# BendulumClockShield.net
KiCad netlist of a schematic drawn in EAGLE
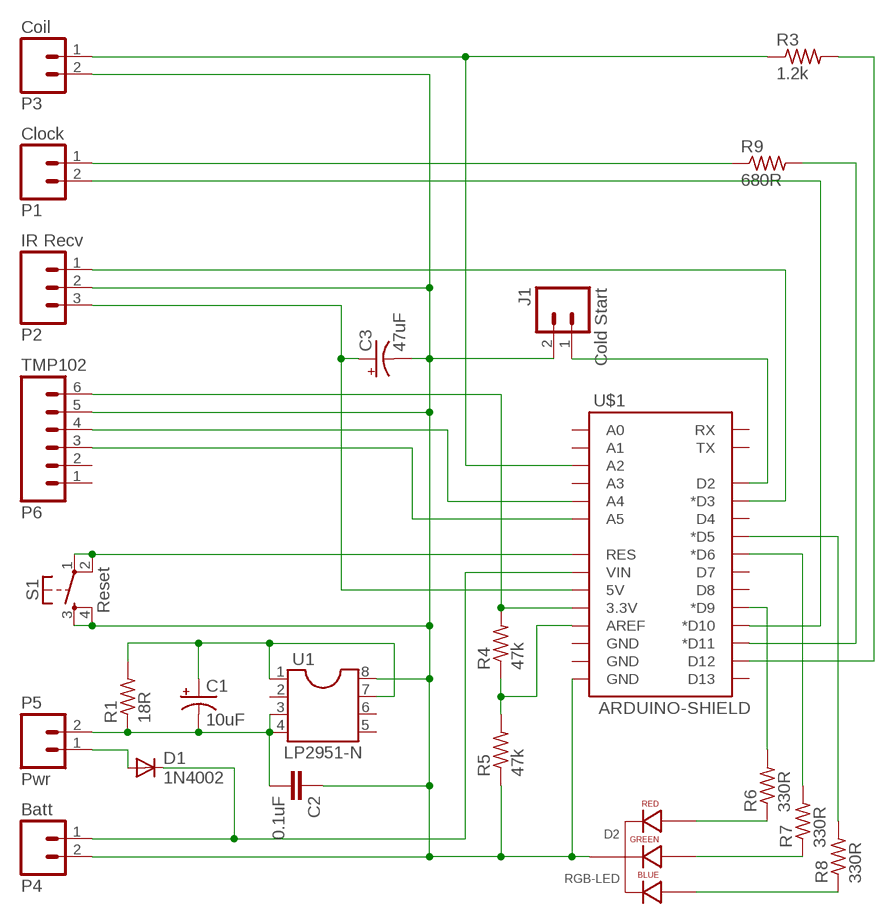
[diagram p0: schematic, sheet 1]

(export (version "E")
  (design (tool "Eeschema 10.0.6"))
  (components
    (comp (ref "C1")
      (value "10uF")
      (footprint "eagle-import:CPOL-RADIAL-10UF-25V")
      (libsource (lib "eagle-import") (part "10UF-25V-20%(PTH)"))
    )
    (comp (ref "C2")
      (value "0.1uF")
      (footprint "eagle-import:CAP-PTH-5MM")
      (libsource (lib "eagle-import") (part "CAPPTH1"))
    )
    (comp (ref "C3")
      (value "47uF")
      (footprint "eagle-import:CPOL-RADIAL-10UF-25V")
      (libsource (lib "eagle-import") (part "10UF-25V-20%(PTH)"))
    )
    (comp (ref "D1")
      (value "1N4002")
      (footprint "eagle-import:DIODE-1N4001-KIT")
      (libsource (lib "eagle-import") (part "DIODE"))
    )
    (comp (ref "D2")
      (value "RGB-LED")
      (footprint "eagle-import:LED-RGB-THRU")
      (libsource (lib "eagle-import") (part "LED-RGB-CC-THRUDIFFUSE"))
    )
    (comp (ref "J1")
      (value "Cold Start")
      (footprint "eagle-import:1X02")
      (libsource (lib "eagle-import") (part "M02PTH"))
    )
    (comp (ref "P1")
      (value "Clock")
      (footprint "eagle-import:1X02")
      (libsource (lib "eagle-import") (part "M02PTH"))
    )
    (comp (ref "P2")
      (value "IR Recv")
      (footprint "eagle-import:1X03")
      (libsource (lib "eagle-import") (part "M03PTH"))
    )
    (comp (ref "P3")
      (value "Coil")
      (footprint "eagle-import:1X02")
      (libsource (lib "eagle-import") (part "M02PTH"))
    )
    (comp (ref "P4")
      (value "Batt")
      (footprint "eagle-import:1X02")
      (libsource (lib "eagle-import") (part "M02PTH"))
    )
    (comp (ref "P5")
      (value "Pwr")
      (footprint "eagle-import:1X02")
      (libsource (lib "eagle-import") (part "M02PTH"))
    )
    (comp (ref "R1")
      (value "18R")
      (footprint "eagle-import:AXIAL-0.4")
      (libsource (lib "eagle-import") (part "R-US_"))
    )
    (comp (ref "R3")
      (value "1.2k")
      (footprint "eagle-import:AXIAL-0.4")
      (libsource (lib "eagle-import") (part "R-US_"))
    )
    (comp (ref "R4")
      (value "47k")
      (footprint "eagle-import:AXIAL-0.4")
      (libsource (lib "eagle-import") (part "R-US_"))
    )
    (comp (ref "R5")
      (value "47k")
      (footprint "eagle-import:AXIAL-0.4")
      (libsource (lib "eagle-import") (part "R-US_"))
    )
    (comp (ref "R6")
      (value "330R")
      (footprint "eagle-import:AXIAL-0.4")
      (libsource (lib "eagle-import") (part "R-US_"))
    )
    (comp (ref "R7")
      (value "330R")
      (footprint "eagle-import:AXIAL-0.4")
      (libsource (lib "eagle-import") (part "R-US_"))
    )
    (comp (ref "R8")
      (value "330R")
      (footprint "eagle-import:AXIAL-0.4")
      (libsource (lib "eagle-import") (part "R-US_"))
    )
    (comp (ref "R9")
      (value "680R")
      (footprint "eagle-import:AXIAL-0.4")
      (libsource (lib "eagle-import") (part "R-US_"))
    )
    (comp (ref "S1")
      (value "Reset")
      (footprint "eagle-import:TACTILE-PTH")
      (libsource (lib "eagle-import") (part "TAC_SWITCHPTH"))
    )
    (comp (ref "TMP102")
      (value "P6")
      (footprint "eagle-import:1X06")
      (libsource (lib "eagle-import") (part "M06SIP"))
    )
    (comp (ref "U$1")
      (value "ARDUINO-SHIELD")
      (footprint "eagle-import:DUEMILANOVE_SHIELD")
      (libsource (lib "eagle-import") (part "ARDUINO-SHIELD"))
    )
    (comp (ref "U1")
      (value "LP2951-N")
      (footprint "eagle-import:SOCKET-08")
      (libsource (lib "eagle-import") (part "LP2951-N"))
    )
  )
  (nets
    (net (code "1") (name "Net-(C1-+)") (class "Default")
      (node (ref "C1") (pin "1") (pinfunction "+_1") (pintype "passive"))
      (node (ref "R1") (pin "P$2") (pinfunction "2_P$2") (pintype "passive"))
      (node (ref "U1") (pin "1") (pinfunction "OUTPUT_1") (pintype "passive"))
      (node (ref "U1") (pin "7") (pinfunction "FEEDBACK_7") (pintype "passive"))
    )
    (net (code "2") (name "Net-(C1--)") (class "Default")
      (node (ref "C1") (pin "2") (pinfunction "-_2") (pintype "passive"))
      (node (ref "C2") (pin "2") (pinfunction "2_2") (pintype "passive"))
      (node (ref "P5") (pin "2") (pinfunction "2_2") (pintype "passive"))
      (node (ref "R1") (pin "P$1") (pinfunction "1_P$1") (pintype "passive"))
      (node (ref "U1") (pin "3") (pinfunction "SHUTDOWN_3") (pintype "passive"))
      (node (ref "U1") (pin "4") (pinfunction "GND_4") (pintype "passive"))
    )
    (net (code "3") (name "Net-(C3-+)") (class "Default")
      (node (ref "C3") (pin "1") (pinfunction "+_1") (pintype "passive"))
      (node (ref "P2") (pin "3") (pinfunction "3_3") (pintype "passive"))
      (node (ref "U$1") (pin "5V") (pinfunction "5V_5V") (pintype "bidirectional"))
    )
    (net (code "4") (name "Net-(C3--)") (class "Default")
      (node (ref "C2") (pin "1") (pinfunction "1_1") (pintype "passive"))
      (node (ref "C3") (pin "2") (pinfunction "-_2") (pintype "passive"))
      (node (ref "D2") (pin "2") (pinfunction "CATHODE_2") (pintype "bidirectional"))
      (node (ref "J1") (pin "2") (pinfunction "2_2") (pintype "passive"))
      (node (ref "P2") (pin "2") (pinfunction "2_2") (pintype "passive"))
      (node (ref "P3") (pin "2") (pinfunction "2_2") (pintype "passive"))
      (node (ref "P4") (pin "2") (pinfunction "2_2") (pintype "passive"))
      (node (ref "R5") (pin "P$1") (pinfunction "1_P$1") (pintype "passive"))
      (node (ref "S1") (pin "3") (pinfunction "3_3") (pintype "passive"))
      (node (ref "S1") (pin "4") (pinfunction "4_4") (pintype "passive"))
      (node (ref "TMP102") (pin "5") (pinfunction "5_5") (pintype "passive"))
      (node (ref "U$1") (pin "GND@0") (pinfunction "GND_GND@0") (pintype "bidirectional"))
      (node (ref "U1") (pin "8") (pinfunction "INPUT_8") (pintype "passive"))
    )
    (net (code "5") (name "Net-(D1-PadA)") (class "Default")
      (node (ref "D1") (pin "A") (pinfunction "A_A") (pintype "passive"))
      (node (ref "P5") (pin "1") (pinfunction "1_1") (pintype "passive"))
    )
    (net (code "6") (name "Net-(D1-PadC)") (class "Default")
      (node (ref "D1") (pin "C") (pinfunction "C_C") (pintype "passive"))
      (node (ref "P4") (pin "1") (pinfunction "1_1") (pintype "passive"))
      (node (ref "U$1") (pin "VIN") (pinfunction "VIN_VIN") (pintype "bidirectional"))
    )
    (net (code "7") (name "Net-(D2-BLUE_ANODE)") (class "Default")
      (node (ref "D2") (pin "4") (pinfunction "BLUE_ANODE_4") (pintype "bidirectional"))
      (node (ref "R8") (pin "P$1") (pinfunction "1_P$1") (pintype "passive"))
    )
    (net (code "8") (name "Net-(D2-GREEN_ANODE)") (class "Default")
      (node (ref "D2") (pin "3") (pinfunction "GREEN_ANODE_3") (pintype "bidirectional"))
      (node (ref "R7") (pin "P$1") (pinfunction "1_P$1") (pintype "passive"))
    )
    (net (code "9") (name "Net-(D2-RED_ANODE)") (class "Default")
      (node (ref "D2") (pin "1") (pinfunction "RED_ANODE_1") (pintype "bidirectional"))
      (node (ref "R6") (pin "P$1") (pinfunction "1_P$1") (pintype "passive"))
    )
    (net (code "10") (name "Net-(J1-Pad1)") (class "Default")
      (node (ref "J1") (pin "1") (pinfunction "1_1") (pintype "passive"))
      (node (ref "U$1") (pin "D2") (pinfunction "D2_D2") (pintype "bidirectional"))
    )
    (net (code "11") (name "Net-(R3-1)") (class "Default")
      (node (ref "P3") (pin "1") (pinfunction "1_1") (pintype "passive"))
      (node (ref "R3") (pin "P$1") (pinfunction "1_P$1") (pintype "passive"))
      (node (ref "U$1") (pin "A2") (pinfunction "A2_A2") (pintype "bidirectional"))
    )
    (net (code "12") (name "Net-(R3-2)") (class "Default")
      (node (ref "R3") (pin "P$2") (pinfunction "2_P$2") (pintype "passive"))
      (node (ref "U$1") (pin "D12") (pinfunction "D12_D12") (pintype "bidirectional"))
    )
    (net (code "13") (name "Net-(R4-1)") (class "Default")
      (node (ref "R4") (pin "P$1") (pinfunction "1_P$1") (pintype "passive"))
      (node (ref "R5") (pin "P$2") (pinfunction "2_P$2") (pintype "passive"))
      (node (ref "U$1") (pin "AREF") (pinfunction "AREF_AREF") (pintype "bidirectional"))
    )
    (net (code "14") (name "Net-(R4-2)") (class "Default")
      (node (ref "R4") (pin "P$2") (pinfunction "2_P$2") (pintype "passive"))
      (node (ref "TMP102") (pin "6") (pinfunction "6_6") (pintype "passive"))
      (node (ref "U$1") (pin "3.3V") (pinfunction "3.3V_3.3V") (pintype "bidirectional"))
    )
    (net (code "15") (name "Net-(R6-2)") (class "Default")
      (node (ref "R6") (pin "P$2") (pinfunction "2_P$2") (pintype "passive"))
      (node (ref "U$1") (pin "D9") (pinfunction "*D9_D9") (pintype "bidirectional"))
    )
    (net (code "16") (name "Net-(R7-2)") (class "Default")
      (node (ref "R7") (pin "P$2") (pinfunction "2_P$2") (pintype "passive"))
      (node (ref "U$1") (pin "D6") (pinfunction "*D6_D6") (pintype "bidirectional"))
    )
    (net (code "17") (name "Net-(R8-2)") (class "Default")
      (node (ref "R8") (pin "P$2") (pinfunction "2_P$2") (pintype "passive"))
      (node (ref "U$1") (pin "D5") (pinfunction "*D5_D5") (pintype "bidirectional"))
    )
    (net (code "18") (name "Net-(R9-1)") (class "Default")
      (node (ref "P1") (pin "1") (pinfunction "1_1") (pintype "passive"))
      (node (ref "R9") (pin "P$1") (pinfunction "1_P$1") (pintype "passive"))
    )
    (net (code "19") (name "Net-(R9-2)") (class "Default")
      (node (ref "R9") (pin "P$2") (pinfunction "2_P$2") (pintype "passive"))
      (node (ref "U$1") (pin "D11") (pinfunction "*D11_D11") (pintype "bidirectional"))
    )
    (net (code "20") (name "Net-(S1-Pad1)") (class "Default")
      (node (ref "S1") (pin "1") (pinfunction "1_1") (pintype "passive"))
      (node (ref "S1") (pin "2") (pinfunction "2_2") (pintype "passive"))
      (node (ref "U$1") (pin "RES") (pinfunction "RES_RES") (pintype "bidirectional"))
    )
    (net (code "21") (name "Net-(TMP102-Pad3)") (class "Default")
      (node (ref "TMP102") (pin "3") (pinfunction "3_3") (pintype "passive"))
      (node (ref "U$1") (pin "A5") (pinfunction "A5_A5") (pintype "bidirectional"))
    )
    (net (code "22") (name "Net-(TMP102-Pad4)") (class "Default")
      (node (ref "TMP102") (pin "4") (pinfunction "4_4") (pintype "passive"))
      (node (ref "U$1") (pin "A4") (pinfunction "A4_A4") (pintype "bidirectional"))
    )
    (net (code "23") (name "Net-(U$1-*D3)") (class "Default")
      (node (ref "P2") (pin "1") (pinfunction "1_1") (pintype "passive"))
      (node (ref "U$1") (pin "D3") (pinfunction "*D3_D3") (pintype "bidirectional"))
    )
    (net (code "24") (name "Net-(U$1-*D10)") (class "Default")
      (node (ref "P1") (pin "2") (pinfunction "2_2") (pintype "passive"))
      (node (ref "U$1") (pin "D10") (pinfunction "*D10_D10") (pintype "bidirectional"))
    )
    (net (code "25") (name "unconnected-(TMP102-Pad1)") (class "Default")
      (node (ref "TMP102") (pin "1") (pinfunction "1_1") (pintype "passive"))
    )
    (net (code "26") (name "unconnected-(TMP102-Pad2)") (class "Default")
      (node (ref "TMP102") (pin "2") (pinfunction "2_2") (pintype "passive"))
    )
    (net (code "27") (name "unconnected-(U$1-GND-PadGND@1)") (class "Default")
      (node (ref "U$1") (pin "GND@1") (pinfunction "GND_GND@1") (pintype "bidirectional"))
    )
    (net (code "28") (name "unconnected-(U$1-GND-PadGND@2)") (class "Default")
      (node (ref "U$1") (pin "GND@2") (pinfunction "GND_GND@2") (pintype "bidirectional"))
    )
    (net (code "29") (name "unconnected-(U$1-PadA0)") (class "Default")
      (node (ref "U$1") (pin "A0") (pinfunction "A0_A0") (pintype "bidirectional"))
    )
    (net (code "30") (name "unconnected-(U$1-PadA1)") (class "Default")
      (node (ref "U$1") (pin "A1") (pinfunction "A1_A1") (pintype "bidirectional"))
    )
    (net (code "31") (name "unconnected-(U$1-PadA3)") (class "Default")
      (node (ref "U$1") (pin "A3") (pinfunction "A3_A3") (pintype "bidirectional"))
    )
    (net (code "32") (name "unconnected-(U$1-PadD4)") (class "Default")
      (node (ref "U$1") (pin "D4") (pinfunction "D4_D4") (pintype "bidirectional"))
    )
    (net (code "33") (name "unconnected-(U$1-PadD7)") (class "Default")
      (node (ref "U$1") (pin "D7") (pinfunction "D7_D7") (pintype "bidirectional"))
    )
    (net (code "34") (name "unconnected-(U$1-PadD8)") (class "Default")
      (node (ref "U$1") (pin "D8") (pinfunction "D8_D8") (pintype "bidirectional"))
    )
    (net (code "35") (name "unconnected-(U$1-PadD13)") (class "Default")
      (node (ref "U$1") (pin "D13") (pinfunction "D13_D13") (pintype "bidirectional"))
    )
    (net (code "36") (name "unconnected-(U$1-PadRX)") (class "Default")
      (node (ref "U$1") (pin "RX") (pinfunction "RX_RX") (pintype "bidirectional"))
    )
    (net (code "37") (name "unconnected-(U$1-PadTX)") (class "Default")
      (node (ref "U$1") (pin "TX") (pinfunction "TX_TX") (pintype "bidirectional"))
    )
    (net (code "38") (name "unconnected-(U1-NOT-ERROR-Pad5)") (class "Default")
      (node (ref "U1") (pin "5") (pinfunction "NOT-ERROR_5") (pintype "passive"))
    )
    (net (code "39") (name "unconnected-(U1-SENSE-Pad2)") (class "Default")
      (node (ref "U1") (pin "2") (pinfunction "SENSE_2") (pintype "passive"))
    )
    (net (code "40") (name "unconnected-(U1-V0-TAP-Pad6)") (class "Default")
      (node (ref "U1") (pin "6") (pinfunction "V0-TAP_6") (pintype "passive"))
    )
  )
)
